# IO2.net
KiCad netlist of a schematic drawn in Altium Designer
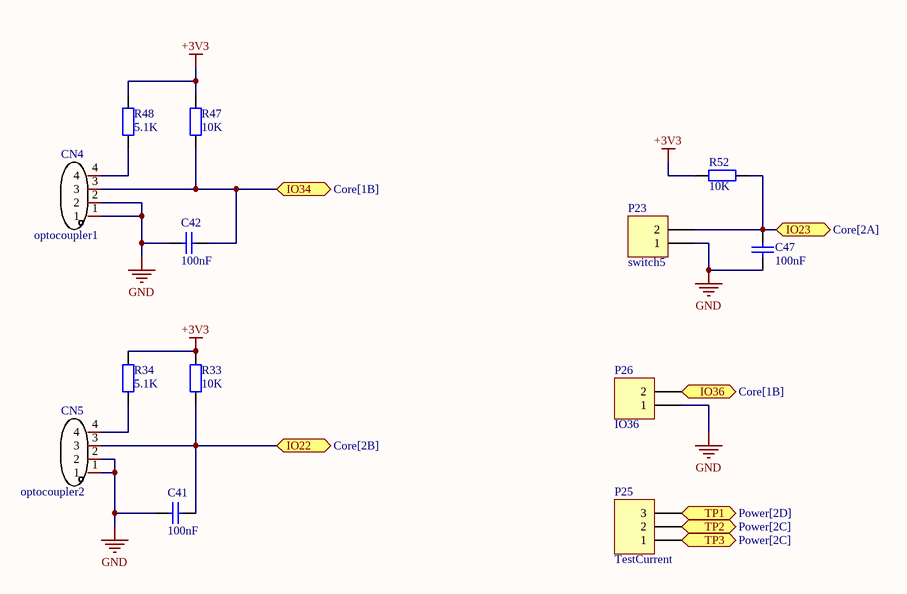
[diagram p0: IO2.SchDoc]

(export (version "E")
  (design (tool "Eeschema 10.0.6"))
  (components
    (comp (ref "C41")
      (value "100nF")
      (footprint "6-0805_N")
      (description "Capacitor")
      (fields (field (name "Comment") "Cap") (field (name "PUBLISHER") "Altium Limited"))
      (libsource (lib "Miscellaneous Devices") (part "Cap"))
    )
    (comp (ref "C42")
      (value "100nF")
      (footprint "6-0805_N")
      (description "Capacitor")
      (fields (field (name "Comment") "Cap") (field (name "PUBLISHER") "Altium Limited"))
      (libsource (lib "Miscellaneous Devices") (part "Cap"))
    )
    (comp (ref "C47")
      (value "100nF")
      (footprint "6-0805_N")
      (description "Capacitor")
      (fields (field (name "Comment") "Cap") (field (name "PUBLISHER") "Altium Limited"))
      (libsource (lib "Miscellaneous Devices") (part "Cap"))
    )
    (comp (ref "CN4")
      (value "ZX-XH2.54-4PZZ")
      (footprint "CONN-TH_4P-P2.50_4PIN")
      (fields (field (name "MANUFACTURER") "Megastar(兆星)") (field (name "NAME") "optocoupler1"))
      (libsource (lib "4PZZ") (part "ZX-XH2.54-4PZZ"))
    )
    (comp (ref "CN5")
      (value "ZX-XH2.54-4PZZ")
      (footprint "CONN-TH_4P-P2.50_4PIN")
      (fields (field (name "MANUFACTURER") "Megastar(兆星)") (field (name "NAME") "optocoupler2"))
      (libsource (lib "4PZZ") (part "ZX-XH2.54-4PZZ"))
    )
    (comp (ref "P23")
      (value "switch5")
      (footprint "HDR1X2")
      (description "Header, 2-Pin")
      (fields (field (name "PUBLISHER") "Altium Limited"))
      (libsource (lib "Miscellaneous Connectors") (part "Header 2"))
    )
    (comp (ref "P25")
      (value "TestCurrent")
      (footprint "HDR1X3")
      (description "Header, 3-Pin")
      (fields (field (name "PUBLISHER") "Altium Limited"))
      (libsource (lib "Miscellaneous Connectors") (part "Header 3"))
    )
    (comp (ref "P26")
      (value "IO36")
      (footprint "HDR1X2")
      (description "Header, 2-Pin")
      (fields (field (name "PUBLISHER") "Altium Limited"))
      (libsource (lib "Miscellaneous Connectors") (part "Header 2"))
    )
    (comp (ref "R33")
      (value "10K")
      (footprint "6-0805_N")
      (description "Resistor")
      (fields (field (name "Comment") "Res2") (field (name "PUBLISHER") "Altium Limited"))
      (libsource (lib "") (part "Res2_1"))
    )
    (comp (ref "R34")
      (value "5.1K")
      (footprint "6-0805_N")
      (description "Resistor")
      (fields (field (name "Comment") "Res2") (field (name "PUBLISHER") "Altium Limited"))
      (libsource (lib "") (part "Res2_1"))
    )
    (comp (ref "R47")
      (value "10K")
      (footprint "6-0805_N")
      (description "Resistor")
      (fields (field (name "Comment") "Res2") (field (name "PUBLISHER") "Altium Limited"))
      (libsource (lib "Miscellaneous Devices") (part "Res2"))
    )
    (comp (ref "R48")
      (value "5.1K")
      (footprint "6-0805_N")
      (description "Resistor")
      (fields (field (name "Comment") "Res2") (field (name "PUBLISHER") "Altium Limited"))
      (libsource (lib "Miscellaneous Devices") (part "Res2"))
    )
    (comp (ref "R52")
      (value "10K")
      (footprint "6-0805_N")
      (description "Resistor")
      (fields (field (name "Comment") "Res2") (field (name "PUBLISHER") "Altium Limited"))
      (libsource (lib "") (part "Res2_2"))
    )
  )
  (nets
    (net (code "1") (name "+3V3") (class "Default")
      (node (ref "R33") (pin "2") (pinfunction "2_2") (pintype "passive"))
      (node (ref "R34") (pin "2") (pinfunction "2_2") (pintype "passive"))
      (node (ref "R47") (pin "1") (pinfunction "1_1") (pintype "passive"))
      (node (ref "R48") (pin "1") (pinfunction "1_1") (pintype "passive"))
      (node (ref "R52") (pin "1") (pinfunction "1_1") (pintype "passive"))
    )
    (net (code "2") (name "/IO22") (class "Default")
      (node (ref "C41") (pin "1") (pinfunction "1_1") (pintype "passive"))
      (node (ref "CN5") (pin "3") (pinfunction "3_3") (pintype "passive"))
      (node (ref "R33") (pin "1") (pinfunction "1_1") (pintype "passive"))
    )
    (net (code "3") (name "/IO23") (class "Default")
      (node (ref "C47") (pin "2") (pinfunction "2_2") (pintype "passive"))
      (node (ref "P23") (pin "2") (pinfunction "2_2") (pintype "passive"))
      (node (ref "R52") (pin "2") (pinfunction "2_2") (pintype "passive"))
    )
    (net (code "4") (name "/IO34") (class "Default")
      (node (ref "C42") (pin "1") (pinfunction "1_1") (pintype "passive"))
      (node (ref "CN4") (pin "3") (pinfunction "3_3") (pintype "passive"))
      (node (ref "R47") (pin "2") (pinfunction "2_2") (pintype "passive"))
    )
    (net (code "5") (name "/IO36") (class "Default")
      (node (ref "P26") (pin "2") (pinfunction "2_2") (pintype "passive"))
    )
    (net (code "6") (name "/TP1") (class "Default")
      (node (ref "P25") (pin "3") (pinfunction "3_3") (pintype "passive"))
    )
    (net (code "7") (name "/TP2") (class "Default")
      (node (ref "P25") (pin "2") (pinfunction "2_2") (pintype "passive"))
    )
    (net (code "8") (name "/TP3") (class "Default")
      (node (ref "P25") (pin "1") (pinfunction "1_1") (pintype "passive"))
    )
    (net (code "9") (name "GND") (class "Default")
      (node (ref "C41") (pin "2") (pinfunction "2_2") (pintype "passive"))
      (node (ref "C42") (pin "2") (pinfunction "2_2") (pintype "passive"))
      (node (ref "C47") (pin "1") (pinfunction "1_1") (pintype "passive"))
      (node (ref "CN4") (pin "1") (pinfunction "1_1") (pintype "passive"))
      (node (ref "CN4") (pin "2") (pinfunction "2_2") (pintype "passive"))
      (node (ref "CN5") (pin "1") (pinfunction "1_1") (pintype "passive"))
      (node (ref "CN5") (pin "2") (pinfunction "2_2") (pintype "passive"))
      (node (ref "P23") (pin "1") (pinfunction "1_1") (pintype "passive"))
      (node (ref "P26") (pin "1") (pinfunction "1_1") (pintype "passive"))
    )
    (net (code "10") (name "Net-(CN4-Pad4)") (class "Default")
      (node (ref "CN4") (pin "4") (pinfunction "4_4") (pintype "passive"))
      (node (ref "R48") (pin "2") (pinfunction "2_2") (pintype "passive"))
    )
    (net (code "11") (name "Net-(CN5-Pad4)") (class "Default")
      (node (ref "CN5") (pin "4") (pinfunction "4_4") (pintype "passive"))
      (node (ref "R34") (pin "1") (pinfunction "1_1") (pintype "passive"))
    )
  )
)
